# MCUs.net
KiCad netlist of a schematic drawn in Altium Designer
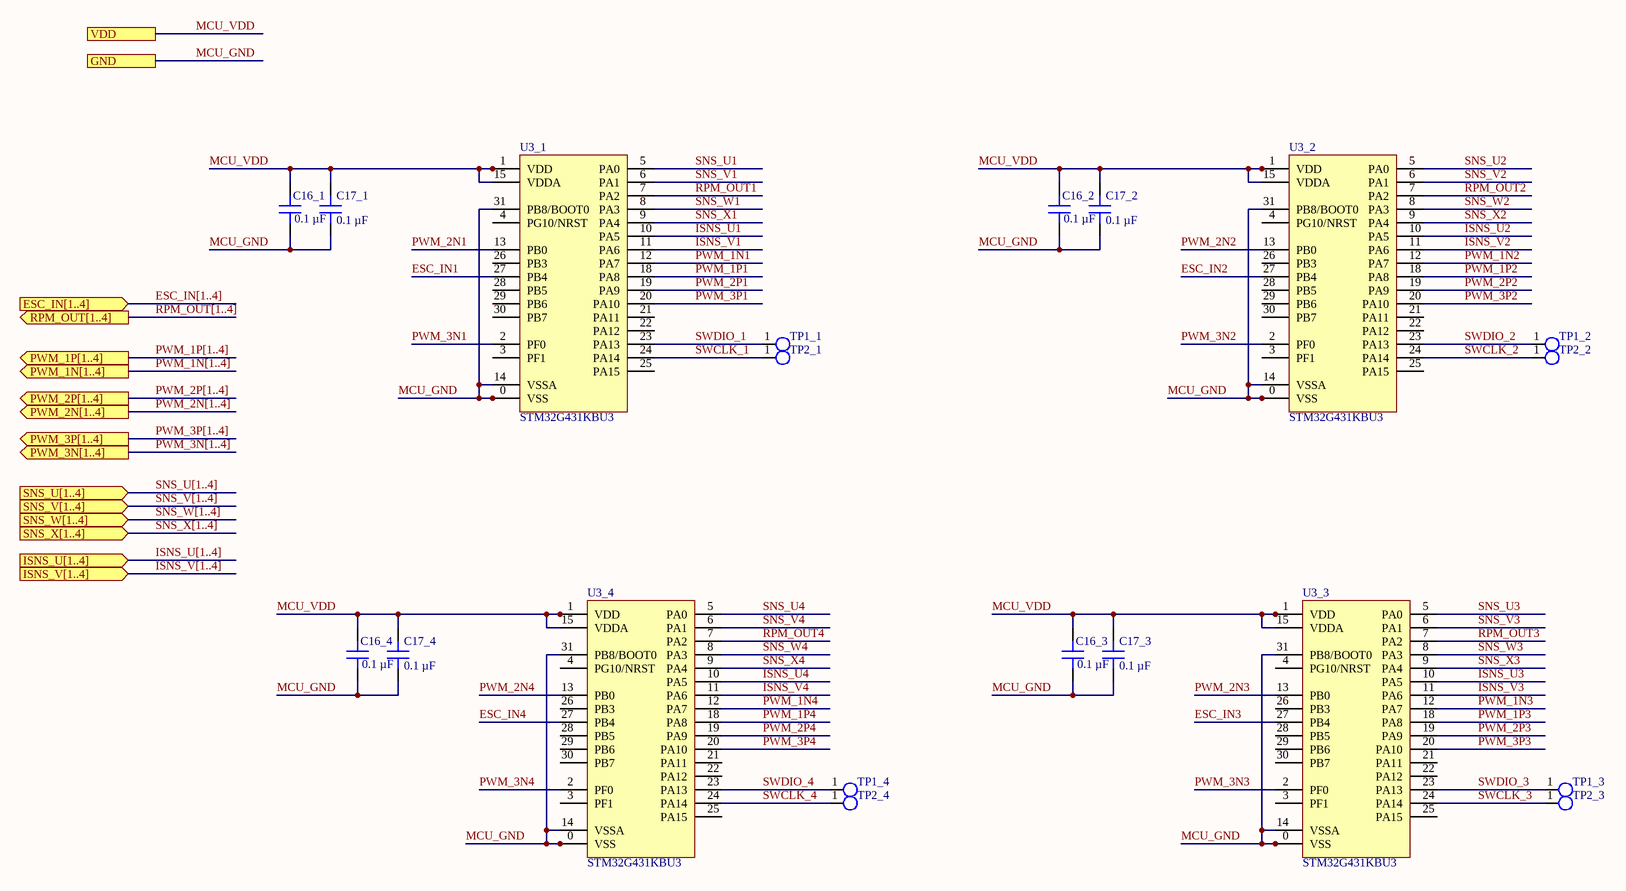
[diagram p0: MCUs.SchDoc]

(export (version "E")
  (design (tool "Eeschema 10.0.6"))
  (components
    (comp (ref "C16_1")
      (value "0.1 µF")
      (footprint "CAP 0402_1005")
      (description "CAP CER 0.1UF 16V X7R 0402")
      (fields (field (name "PART NUMBER") "C0402C104K4RACAUTO") (field (name "MANUFACTURER") "KEMET"))
      (libsource (lib "Celestial Altium Library - altium_library") (part "Capacitor"))
    )
    (comp (ref "C16_2")
      (value "0.1 µF")
      (footprint "CAP 0402_1005")
      (description "CAP CER 0.1UF 16V X7R 0402")
      (fields (field (name "PART NUMBER") "C0402C104K4RACAUTO") (field (name "MANUFACTURER") "KEMET"))
      (libsource (lib "Celestial Altium Library - altium_library") (part "Capacitor"))
    )
    (comp (ref "C16_3")
      (value "0.1 µF")
      (footprint "CAP 0402_1005")
      (description "CAP CER 0.1UF 16V X7R 0402")
      (fields (field (name "PART NUMBER") "C0402C104K4RACAUTO") (field (name "MANUFACTURER") "KEMET"))
      (libsource (lib "Celestial Altium Library - altium_library") (part "Capacitor"))
    )
    (comp (ref "C16_4")
      (value "0.1 µF")
      (footprint "CAP 0402_1005")
      (description "CAP CER 0.1UF 16V X7R 0402")
      (fields (field (name "PART NUMBER") "C0402C104K4RACAUTO") (field (name "MANUFACTURER") "KEMET"))
      (libsource (lib "Celestial Altium Library - altium_library") (part "Capacitor"))
    )
    (comp (ref "C17_1")
      (value "0.1 µF")
      (footprint "CAP 0402_1005")
      (description "CAP CER 0.1UF 16V X7R 0402")
      (fields (field (name "PART NUMBER") "C0402C104K4RACAUTO") (field (name "MANUFACTURER") "KEMET"))
      (libsource (lib "Celestial Altium Library - altium_library") (part "Capacitor"))
    )
    (comp (ref "C17_2")
      (value "0.1 µF")
      (footprint "CAP 0402_1005")
      (description "CAP CER 0.1UF 16V X7R 0402")
      (fields (field (name "PART NUMBER") "C0402C104K4RACAUTO") (field (name "MANUFACTURER") "KEMET"))
      (libsource (lib "Celestial Altium Library - altium_library") (part "Capacitor"))
    )
    (comp (ref "C17_3")
      (value "0.1 µF")
      (footprint "CAP 0402_1005")
      (description "CAP CER 0.1UF 16V X7R 0402")
      (fields (field (name "PART NUMBER") "C0402C104K4RACAUTO") (field (name "MANUFACTURER") "KEMET"))
      (libsource (lib "Celestial Altium Library - altium_library") (part "Capacitor"))
    )
    (comp (ref "C17_4")
      (value "0.1 µF")
      (footprint "CAP 0402_1005")
      (description "CAP CER 0.1UF 16V X7R 0402")
      (fields (field (name "PART NUMBER") "C0402C104K4RACAUTO") (field (name "MANUFACTURER") "KEMET"))
      (libsource (lib "Celestial Altium Library - altium_library") (part "Capacitor"))
    )
    (comp (ref "TP1_1")
      (value "0.635mm")
      (footprint "TP  0.635mm")
      (description "Test point")
      (libsource (lib "IC") (part "TP 0.635mm"))
    )
    (comp (ref "TP1_2")
      (value "0.635mm")
      (footprint "TP  0.635mm")
      (description "Test point")
      (libsource (lib "IC") (part "TP 0.635mm"))
    )
    (comp (ref "TP1_3")
      (value "0.635mm")
      (footprint "TP  0.635mm")
      (description "Test point")
      (libsource (lib "IC") (part "TP 0.635mm"))
    )
    (comp (ref "TP1_4")
      (value "0.635mm")
      (footprint "TP  0.635mm")
      (description "Test point")
      (libsource (lib "IC") (part "TP 0.635mm"))
    )
    (comp (ref "TP2_1")
      (value "0.635mm")
      (footprint "TP  0.635mm")
      (description "Test point")
      (libsource (lib "IC") (part "TP 0.635mm"))
    )
    (comp (ref "TP2_2")
      (value "0.635mm")
      (footprint "TP  0.635mm")
      (description "Test point")
      (libsource (lib "IC") (part "TP 0.635mm"))
    )
    (comp (ref "TP2_3")
      (value "0.635mm")
      (footprint "TP  0.635mm")
      (description "Test point")
      (libsource (lib "IC") (part "TP 0.635mm"))
    )
    (comp (ref "TP2_4")
      (value "0.635mm")
      (footprint "TP  0.635mm")
      (description "Test point")
      (libsource (lib "IC") (part "TP 0.635mm"))
    )
    (comp (ref "U3_1")
      (value "STM32G431KBU3")
      (footprint "QFN50P400X400X60-32N")
      (description "MCU UFQFPN-32")
      (libsource (lib "IC") (part "STM32G431KBU3"))
    )
    (comp (ref "U3_2")
      (value "STM32G431KBU3")
      (footprint "QFN50P400X400X60-32N")
      (description "MCU UFQFPN-32")
      (libsource (lib "IC") (part "STM32G431KBU3"))
    )
    (comp (ref "U3_3")
      (value "STM32G431KBU3")
      (footprint "QFN50P400X400X60-32N")
      (description "MCU UFQFPN-32")
      (libsource (lib "IC") (part "STM32G431KBU3"))
    )
    (comp (ref "U3_4")
      (value "STM32G431KBU3")
      (footprint "QFN50P400X400X60-32N")
      (description "MCU UFQFPN-32")
      (libsource (lib "IC") (part "STM32G431KBU3"))
    )
  )
  (nets
    (net (code "1") (name "/ESC_IN1") (class "Default")
      (node (ref "U3_1") (pin "27") (pinfunction "PB4_27") (pintype "passive"))
    )
    (net (code "2") (name "/ESC_IN2") (class "Default")
      (node (ref "U3_2") (pin "27") (pinfunction "PB4_27") (pintype "passive"))
    )
    (net (code "3") (name "/ESC_IN3") (class "Default")
      (node (ref "U3_3") (pin "27") (pinfunction "PB4_27") (pintype "passive"))
    )
    (net (code "4") (name "/ESC_IN4") (class "Default")
      (node (ref "U3_4") (pin "27") (pinfunction "PB4_27") (pintype "passive"))
    )
    (net (code "6") (name "/ISNS_U1") (class "Default")
      (node (ref "U3_1") (pin "10") (pinfunction "PA5_10") (pintype "passive"))
    )
    (net (code "7") (name "/ISNS_U2") (class "Default")
      (node (ref "U3_2") (pin "10") (pinfunction "PA5_10") (pintype "passive"))
    )
    (net (code "8") (name "/ISNS_U3") (class "Default")
      (node (ref "U3_3") (pin "10") (pinfunction "PA5_10") (pintype "passive"))
    )
    (net (code "9") (name "/ISNS_U4") (class "Default")
      (node (ref "U3_4") (pin "10") (pinfunction "PA5_10") (pintype "passive"))
    )
    (net (code "11") (name "/ISNS_V1") (class "Default")
      (node (ref "U3_1") (pin "11") (pinfunction "PA6_11") (pintype "passive"))
    )
    (net (code "12") (name "/ISNS_V2") (class "Default")
      (node (ref "U3_2") (pin "11") (pinfunction "PA6_11") (pintype "passive"))
    )
    (net (code "13") (name "/ISNS_V3") (class "Default")
      (node (ref "U3_3") (pin "11") (pinfunction "PA6_11") (pintype "passive"))
    )
    (net (code "14") (name "/ISNS_V4") (class "Default")
      (node (ref "U3_4") (pin "11") (pinfunction "PA6_11") (pintype "passive"))
    )
    (net (code "16") (name "/MCU_GND") (class "Default")
      (node (ref "C16_1") (pin "1") (pinfunction "1_1") (pintype "passive"))
      (node (ref "C16_2") (pin "1") (pinfunction "1_1") (pintype "passive"))
      (node (ref "C16_3") (pin "1") (pinfunction "1_1") (pintype "passive"))
      (node (ref "C16_4") (pin "1") (pinfunction "1_1") (pintype "passive"))
      (node (ref "C17_1") (pin "1") (pinfunction "1_1") (pintype "passive"))
      (node (ref "C17_2") (pin "1") (pinfunction "1_1") (pintype "passive"))
      (node (ref "C17_3") (pin "1") (pinfunction "1_1") (pintype "passive"))
      (node (ref "C17_4") (pin "1") (pinfunction "1_1") (pintype "passive"))
      (node (ref "U3_1") (pin "0") (pinfunction "VSS_0") (pintype "passive"))
      (node (ref "U3_1") (pin "14") (pinfunction "VSSA_14") (pintype "passive"))
      (node (ref "U3_1") (pin "16") (pinfunction "VSS_16") (pintype "passive"))
      (node (ref "U3_1") (pin "31") (pinfunction "PB8/BOOT0_31") (pintype "passive"))
      (node (ref "U3_1") (pin "32") (pinfunction "VSS_32") (pintype "passive"))
      (node (ref "U3_2") (pin "0") (pinfunction "VSS_0") (pintype "passive"))
      (node (ref "U3_2") (pin "14") (pinfunction "VSSA_14") (pintype "passive"))
      (node (ref "U3_2") (pin "16") (pinfunction "VSS_16") (pintype "passive"))
      (node (ref "U3_2") (pin "31") (pinfunction "PB8/BOOT0_31") (pintype "passive"))
      (node (ref "U3_2") (pin "32") (pinfunction "VSS_32") (pintype "passive"))
      (node (ref "U3_3") (pin "0") (pinfunction "VSS_0") (pintype "passive"))
      (node (ref "U3_3") (pin "14") (pinfunction "VSSA_14") (pintype "passive"))
      (node (ref "U3_3") (pin "16") (pinfunction "VSS_16") (pintype "passive"))
      (node (ref "U3_3") (pin "31") (pinfunction "PB8/BOOT0_31") (pintype "passive"))
      (node (ref "U3_3") (pin "32") (pinfunction "VSS_32") (pintype "passive"))
      (node (ref "U3_4") (pin "0") (pinfunction "VSS_0") (pintype "passive"))
      (node (ref "U3_4") (pin "14") (pinfunction "VSSA_14") (pintype "passive"))
      (node (ref "U3_4") (pin "16") (pinfunction "VSS_16") (pintype "passive"))
      (node (ref "U3_4") (pin "31") (pinfunction "PB8/BOOT0_31") (pintype "passive"))
      (node (ref "U3_4") (pin "32") (pinfunction "VSS_32") (pintype "passive"))
    )
    (net (code "17") (name "/MCU_VDD") (class "Default")
      (node (ref "C16_1") (pin "2") (pinfunction "2_2") (pintype "passive"))
      (node (ref "C16_2") (pin "2") (pinfunction "2_2") (pintype "passive"))
      (node (ref "C16_3") (pin "2") (pinfunction "2_2") (pintype "passive"))
      (node (ref "C16_4") (pin "2") (pinfunction "2_2") (pintype "passive"))
      (node (ref "C17_1") (pin "2") (pinfunction "2_2") (pintype "passive"))
      (node (ref "C17_2") (pin "2") (pinfunction "2_2") (pintype "passive"))
      (node (ref "C17_3") (pin "2") (pinfunction "2_2") (pintype "passive"))
      (node (ref "C17_4") (pin "2") (pinfunction "2_2") (pintype "passive"))
      (node (ref "U3_1") (pin "1") (pinfunction "VDD_1") (pintype "passive"))
      (node (ref "U3_1") (pin "15") (pinfunction "VDDA_15") (pintype "passive"))
      (node (ref "U3_1") (pin "17") (pinfunction "VDD_17") (pintype "passive"))
      (node (ref "U3_2") (pin "1") (pinfunction "VDD_1") (pintype "passive"))
      (node (ref "U3_2") (pin "15") (pinfunction "VDDA_15") (pintype "passive"))
      (node (ref "U3_2") (pin "17") (pinfunction "VDD_17") (pintype "passive"))
      (node (ref "U3_3") (pin "1") (pinfunction "VDD_1") (pintype "passive"))
      (node (ref "U3_3") (pin "15") (pinfunction "VDDA_15") (pintype "passive"))
      (node (ref "U3_3") (pin "17") (pinfunction "VDD_17") (pintype "passive"))
      (node (ref "U3_4") (pin "1") (pinfunction "VDD_1") (pintype "passive"))
      (node (ref "U3_4") (pin "15") (pinfunction "VDDA_15") (pintype "passive"))
      (node (ref "U3_4") (pin "17") (pinfunction "VDD_17") (pintype "passive"))
    )
    (net (code "18") (name "/PWM_1N1") (class "Default")
      (node (ref "U3_1") (pin "12") (pinfunction "PA7_12") (pintype "passive"))
    )
    (net (code "19") (name "/PWM_1N2") (class "Default")
      (node (ref "U3_2") (pin "12") (pinfunction "PA7_12") (pintype "passive"))
    )
    (net (code "20") (name "/PWM_1N3") (class "Default")
      (node (ref "U3_3") (pin "12") (pinfunction "PA7_12") (pintype "passive"))
    )
    (net (code "21") (name "/PWM_1N4") (class "Default")
      (node (ref "U3_4") (pin "12") (pinfunction "PA7_12") (pintype "passive"))
    )
    (net (code "23") (name "/PWM_1P1") (class "Default")
      (node (ref "U3_1") (pin "18") (pinfunction "PA8_18") (pintype "passive"))
    )
    (net (code "24") (name "/PWM_1P2") (class "Default")
      (node (ref "U3_2") (pin "18") (pinfunction "PA8_18") (pintype "passive"))
    )
    (net (code "25") (name "/PWM_1P3") (class "Default")
      (node (ref "U3_3") (pin "18") (pinfunction "PA8_18") (pintype "passive"))
    )
    (net (code "26") (name "/PWM_1P4") (class "Default")
      (node (ref "U3_4") (pin "18") (pinfunction "PA8_18") (pintype "passive"))
    )
    (net (code "28") (name "/PWM_2N1") (class "Default")
      (node (ref "U3_1") (pin "13") (pinfunction "PB0_13") (pintype "passive"))
    )
    (net (code "29") (name "/PWM_2N2") (class "Default")
      (node (ref "U3_2") (pin "13") (pinfunction "PB0_13") (pintype "passive"))
    )
    (net (code "30") (name "/PWM_2N3") (class "Default")
      (node (ref "U3_3") (pin "13") (pinfunction "PB0_13") (pintype "passive"))
    )
    (net (code "31") (name "/PWM_2N4") (class "Default")
      (node (ref "U3_4") (pin "13") (pinfunction "PB0_13") (pintype "passive"))
    )
    (net (code "33") (name "/PWM_2P1") (class "Default")
      (node (ref "U3_1") (pin "19") (pinfunction "PA9_19") (pintype "passive"))
    )
    (net (code "34") (name "/PWM_2P2") (class "Default")
      (node (ref "U3_2") (pin "19") (pinfunction "PA9_19") (pintype "passive"))
    )
    (net (code "35") (name "/PWM_2P3") (class "Default")
      (node (ref "U3_3") (pin "19") (pinfunction "PA9_19") (pintype "passive"))
    )
    (net (code "36") (name "/PWM_2P4") (class "Default")
      (node (ref "U3_4") (pin "19") (pinfunction "PA9_19") (pintype "passive"))
    )
    (net (code "38") (name "/PWM_3N1") (class "Default")
      (node (ref "U3_1") (pin "2") (pinfunction "PF0_2") (pintype "passive"))
    )
    (net (code "39") (name "/PWM_3N2") (class "Default")
      (node (ref "U3_2") (pin "2") (pinfunction "PF0_2") (pintype "passive"))
    )
    (net (code "40") (name "/PWM_3N3") (class "Default")
      (node (ref "U3_3") (pin "2") (pinfunction "PF0_2") (pintype "passive"))
    )
    (net (code "41") (name "/PWM_3N4") (class "Default")
      (node (ref "U3_4") (pin "2") (pinfunction "PF0_2") (pintype "passive"))
    )
    (net (code "43") (name "/PWM_3P1") (class "Default")
      (node (ref "U3_1") (pin "20") (pinfunction "PA10_20") (pintype "passive"))
    )
    (net (code "44") (name "/PWM_3P2") (class "Default")
      (node (ref "U3_2") (pin "20") (pinfunction "PA10_20") (pintype "passive"))
    )
    (net (code "45") (name "/PWM_3P3") (class "Default")
      (node (ref "U3_3") (pin "20") (pinfunction "PA10_20") (pintype "passive"))
    )
    (net (code "46") (name "/PWM_3P4") (class "Default")
      (node (ref "U3_4") (pin "20") (pinfunction "PA10_20") (pintype "passive"))
    )
    (net (code "48") (name "/RPM_OUT1") (class "Default")
      (node (ref "U3_1") (pin "7") (pinfunction "PA2_7") (pintype "passive"))
    )
    (net (code "49") (name "/RPM_OUT2") (class "Default")
      (node (ref "U3_2") (pin "7") (pinfunction "PA2_7") (pintype "passive"))
    )
    (net (code "50") (name "/RPM_OUT3") (class "Default")
      (node (ref "U3_3") (pin "7") (pinfunction "PA2_7") (pintype "passive"))
    )
    (net (code "51") (name "/RPM_OUT4") (class "Default")
      (node (ref "U3_4") (pin "7") (pinfunction "PA2_7") (pintype "passive"))
    )
    (net (code "53") (name "/SNS_U1") (class "Default")
      (node (ref "U3_1") (pin "5") (pinfunction "PA0_5") (pintype "passive"))
    )
    (net (code "54") (name "/SNS_U2") (class "Default")
      (node (ref "U3_2") (pin "5") (pinfunction "PA0_5") (pintype "passive"))
    )
    (net (code "55") (name "/SNS_U3") (class "Default")
      (node (ref "U3_3") (pin "5") (pinfunction "PA0_5") (pintype "passive"))
    )
    (net (code "56") (name "/SNS_U4") (class "Default")
      (node (ref "U3_4") (pin "5") (pinfunction "PA0_5") (pintype "passive"))
    )
    (net (code "58") (name "/SNS_V1") (class "Default")
      (node (ref "U3_1") (pin "6") (pinfunction "PA1_6") (pintype "passive"))
    )
    (net (code "59") (name "/SNS_V2") (class "Default")
      (node (ref "U3_2") (pin "6") (pinfunction "PA1_6") (pintype "passive"))
    )
    (net (code "60") (name "/SNS_V3") (class "Default")
      (node (ref "U3_3") (pin "6") (pinfunction "PA1_6") (pintype "passive"))
    )
    (net (code "61") (name "/SNS_V4") (class "Default")
      (node (ref "U3_4") (pin "6") (pinfunction "PA1_6") (pintype "passive"))
    )
    (net (code "63") (name "/SNS_W1") (class "Default")
      (node (ref "U3_1") (pin "8") (pinfunction "PA3_8") (pintype "passive"))
    )
    (net (code "64") (name "/SNS_W2") (class "Default")
      (node (ref "U3_2") (pin "8") (pinfunction "PA3_8") (pintype "passive"))
    )
    (net (code "65") (name "/SNS_W3") (class "Default")
      (node (ref "U3_3") (pin "8") (pinfunction "PA3_8") (pintype "passive"))
    )
    (net (code "66") (name "/SNS_W4") (class "Default")
      (node (ref "U3_4") (pin "8") (pinfunction "PA3_8") (pintype "passive"))
    )
    (net (code "68") (name "/SNS_X1") (class "Default")
      (node (ref "U3_1") (pin "9") (pinfunction "PA4_9") (pintype "passive"))
    )
    (net (code "69") (name "/SNS_X2") (class "Default")
      (node (ref "U3_2") (pin "9") (pinfunction "PA4_9") (pintype "passive"))
    )
    (net (code "70") (name "/SNS_X3") (class "Default")
      (node (ref "U3_3") (pin "9") (pinfunction "PA4_9") (pintype "passive"))
    )
    (net (code "71") (name "/SNS_X4") (class "Default")
      (node (ref "U3_4") (pin "9") (pinfunction "PA4_9") (pintype "passive"))
    )
    (net (code "73") (name "/SWCLK_1") (class "Default")
      (node (ref "TP2_1") (pin "1") (pinfunction "TP_1") (pintype "passive"))
      (node (ref "U3_1") (pin "24") (pinfunction "PA14_24") (pintype "passive"))
    )
    (net (code "74") (name "/SWCLK_2") (class "Default")
      (node (ref "TP2_2") (pin "1") (pinfunction "TP_1") (pintype "passive"))
      (node (ref "U3_2") (pin "24") (pinfunction "PA14_24") (pintype "passive"))
    )
    (net (code "75") (name "/SWCLK_3") (class "Default")
      (node (ref "TP2_3") (pin "1") (pinfunction "TP_1") (pintype "passive"))
      (node (ref "U3_3") (pin "24") (pinfunction "PA14_24") (pintype "passive"))
    )
    (net (code "76") (name "/SWCLK_4") (class "Default")
      (node (ref "TP2_4") (pin "1") (pinfunction "TP_1") (pintype "passive"))
      (node (ref "U3_4") (pin "24") (pinfunction "PA14_24") (pintype "passive"))
    )
    (net (code "77") (name "/SWDIO_1") (class "Default")
      (node (ref "TP1_1") (pin "1") (pinfunction "TP_1") (pintype "passive"))
      (node (ref "U3_1") (pin "23") (pinfunction "PA13_23") (pintype "passive"))
    )
    (net (code "78") (name "/SWDIO_2") (class "Default")
      (node (ref "TP1_2") (pin "1") (pinfunction "TP_1") (pintype "passive"))
      (node (ref "U3_2") (pin "23") (pinfunction "PA13_23") (pintype "passive"))
    )
    (net (code "79") (name "/SWDIO_3") (class "Default")
      (node (ref "TP1_3") (pin "1") (pinfunction "TP_1") (pintype "passive"))
      (node (ref "U3_3") (pin "23") (pinfunction "PA13_23") (pintype "passive"))
    )
    (net (code "80") (name "/SWDIO_4") (class "Default")
      (node (ref "TP1_4") (pin "1") (pinfunction "TP_1") (pintype "passive"))
      (node (ref "U3_4") (pin "23") (pinfunction "PA13_23") (pintype "passive"))
    )
    (net (code "81") (name "unconnected-(U3_1-PA11-Pad21)") (class "Default")
      (node (ref "U3_1") (pin "21") (pinfunction "PA11_21") (pintype "passive"))
    )
    (net (code "82") (name "unconnected-(U3_1-PA12-Pad22)") (class "Default")
      (node (ref "U3_1") (pin "22") (pinfunction "PA12_22") (pintype "passive"))
    )
    (net (code "83") (name "unconnected-(U3_1-PA15-Pad25)") (class "Default")
      (node (ref "U3_1") (pin "25") (pinfunction "PA15_25") (pintype "passive"))
    )
    (net (code "84") (name "unconnected-(U3_1-PB3-Pad26)") (class "Default")
      (node (ref "U3_1") (pin "26") (pinfunction "PB3_26") (pintype "passive"))
    )
    (net (code "85") (name "unconnected-(U3_1-PB5-Pad28)") (class "Default")
      (node (ref "U3_1") (pin "28") (pinfunction "PB5_28") (pintype "passive"))
    )
    (net (code "86") (name "unconnected-(U3_1-PB6-Pad29)") (class "Default")
      (node (ref "U3_1") (pin "29") (pinfunction "PB6_29") (pintype "passive"))
    )
    (net (code "87") (name "unconnected-(U3_1-PB7-Pad30)") (class "Default")
      (node (ref "U3_1") (pin "30") (pinfunction "PB7_30") (pintype "passive"))
    )
    (net (code "88") (name "unconnected-(U3_1-PF1-Pad3)") (class "Default")
      (node (ref "U3_1") (pin "3") (pinfunction "PF1_3") (pintype "passive"))
    )
    (net (code "89") (name "unconnected-(U3_1-PG10{slash}NRST-Pad4)") (class "Default")
      (node (ref "U3_1") (pin "4") (pinfunction "PG10/NRST_4") (pintype "passive"))
    )
    (net (code "90") (name "unconnected-(U3_2-PA11-Pad21)") (class "Default")
      (node (ref "U3_2") (pin "21") (pinfunction "PA11_21") (pintype "passive"))
    )
    (net (code "91") (name "unconnected-(U3_2-PA12-Pad22)") (class "Default")
      (node (ref "U3_2") (pin "22") (pinfunction "PA12_22") (pintype "passive"))
    )
    (net (code "92") (name "unconnected-(U3_2-PA15-Pad25)") (class "Default")
      (node (ref "U3_2") (pin "25") (pinfunction "PA15_25") (pintype "passive"))
    )
    (net (code "93") (name "unconnected-(U3_2-PB3-Pad26)") (class "Default")
      (node (ref "U3_2") (pin "26") (pinfunction "PB3_26") (pintype "passive"))
    )
    (net (code "94") (name "unconnected-(U3_2-PB5-Pad28)") (class "Default")
      (node (ref "U3_2") (pin "28") (pinfunction "PB5_28") (pintype "passive"))
    )
    (net (code "95") (name "unconnected-(U3_2-PB6-Pad29)") (class "Default")
      (node (ref "U3_2") (pin "29") (pinfunction "PB6_29") (pintype "passive"))
    )
    (net (code "96") (name "unconnected-(U3_2-PB7-Pad30)") (class "Default")
      (node (ref "U3_2") (pin "30") (pinfunction "PB7_30") (pintype "passive"))
    )
    (net (code "97") (name "unconnected-(U3_2-PF1-Pad3)") (class "Default")
      (node (ref "U3_2") (pin "3") (pinfunction "PF1_3") (pintype "passive"))
    )
    (net (code "98") (name "unconnected-(U3_2-PG10{slash}NRST-Pad4)") (class "Default")
      (node (ref "U3_2") (pin "4") (pinfunction "PG10/NRST_4") (pintype "passive"))
    )
    (net (code "99") (name "unconnected-(U3_3-PA11-Pad21)") (class "Default")
      (node (ref "U3_3") (pin "21") (pinfunction "PA11_21") (pintype "passive"))
    )
    (net (code "100") (name "unconnected-(U3_3-PA12-Pad22)") (class "Default")
      (node (ref "U3_3") (pin "22") (pinfunction "PA12_22") (pintype "passive"))
    )
    (net (code "101") (name "unconnected-(U3_3-PA15-Pad25)") (class "Default")
      (node (ref "U3_3") (pin "25") (pinfunction "PA15_25") (pintype "passive"))
    )
    (net (code "102") (name "unconnected-(U3_3-PB3-Pad26)") (class "Default")
      (node (ref "U3_3") (pin "26") (pinfunction "PB3_26") (pintype "passive"))
    )
    (net (code "103") (name "unconnected-(U3_3-PB5-Pad28)") (class "Default")
      (node (ref "U3_3") (pin "28") (pinfunction "PB5_28") (pintype "passive"))
    )
    (net (code "104") (name "unconnected-(U3_3-PB6-Pad29)") (class "Default")
      (node (ref "U3_3") (pin "29") (pinfunction "PB6_29") (pintype "passive"))
    )
    (net (code "105") (name "unconnected-(U3_3-PB7-Pad30)") (class "Default")
      (node (ref "U3_3") (pin "30") (pinfunction "PB7_30") (pintype "passive"))
    )
    (net (code "106") (name "unconnected-(U3_3-PF1-Pad3)") (class "Default")
      (node (ref "U3_3") (pin "3") (pinfunction "PF1_3") (pintype "passive"))
    )
    (net (code "107") (name "unconnected-(U3_3-PG10{slash}NRST-Pad4)") (class "Default")
      (node (ref "U3_3") (pin "4") (pinfunction "PG10/NRST_4") (pintype "passive"))
    )
    (net (code "108") (name "unconnected-(U3_4-PA11-Pad21)") (class "Default")
      (node (ref "U3_4") (pin "21") (pinfunction "PA11_21") (pintype "passive"))
    )
    (net (code "109") (name "unconnected-(U3_4-PA12-Pad22)") (class "Default")
      (node (ref "U3_4") (pin "22") (pinfunction "PA12_22") (pintype "passive"))
    )
    (net (code "110") (name "unconnected-(U3_4-PA15-Pad25)") (class "Default")
      (node (ref "U3_4") (pin "25") (pinfunction "PA15_25") (pintype "passive"))
    )
    (net (code "111") (name "unconnected-(U3_4-PB3-Pad26)") (class "Default")
      (node (ref "U3_4") (pin "26") (pinfunction "PB3_26") (pintype "passive"))
    )
    (net (code "112") (name "unconnected-(U3_4-PB5-Pad28)") (class "Default")
      (node (ref "U3_4") (pin "28") (pinfunction "PB5_28") (pintype "passive"))
    )
    (net (code "113") (name "unconnected-(U3_4-PB6-Pad29)") (class "Default")
      (node (ref "U3_4") (pin "29") (pinfunction "PB6_29") (pintype "passive"))
    )
    (net (code "114") (name "unconnected-(U3_4-PB7-Pad30)") (class "Default")
      (node (ref "U3_4") (pin "30") (pinfunction "PB7_30") (pintype "passive"))
    )
    (net (code "115") (name "unconnected-(U3_4-PF1-Pad3)") (class "Default")
      (node (ref "U3_4") (pin "3") (pinfunction "PF1_3") (pintype "passive"))
    )
    (net (code "116") (name "unconnected-(U3_4-PG10{slash}NRST-Pad4)") (class "Default")
      (node (ref "U3_4") (pin "4") (pinfunction "PG10/NRST_4") (pintype "passive"))
    )
  )
)
